# dcfsim.net
KiCad netlist of a schematic drawn in EAGLE
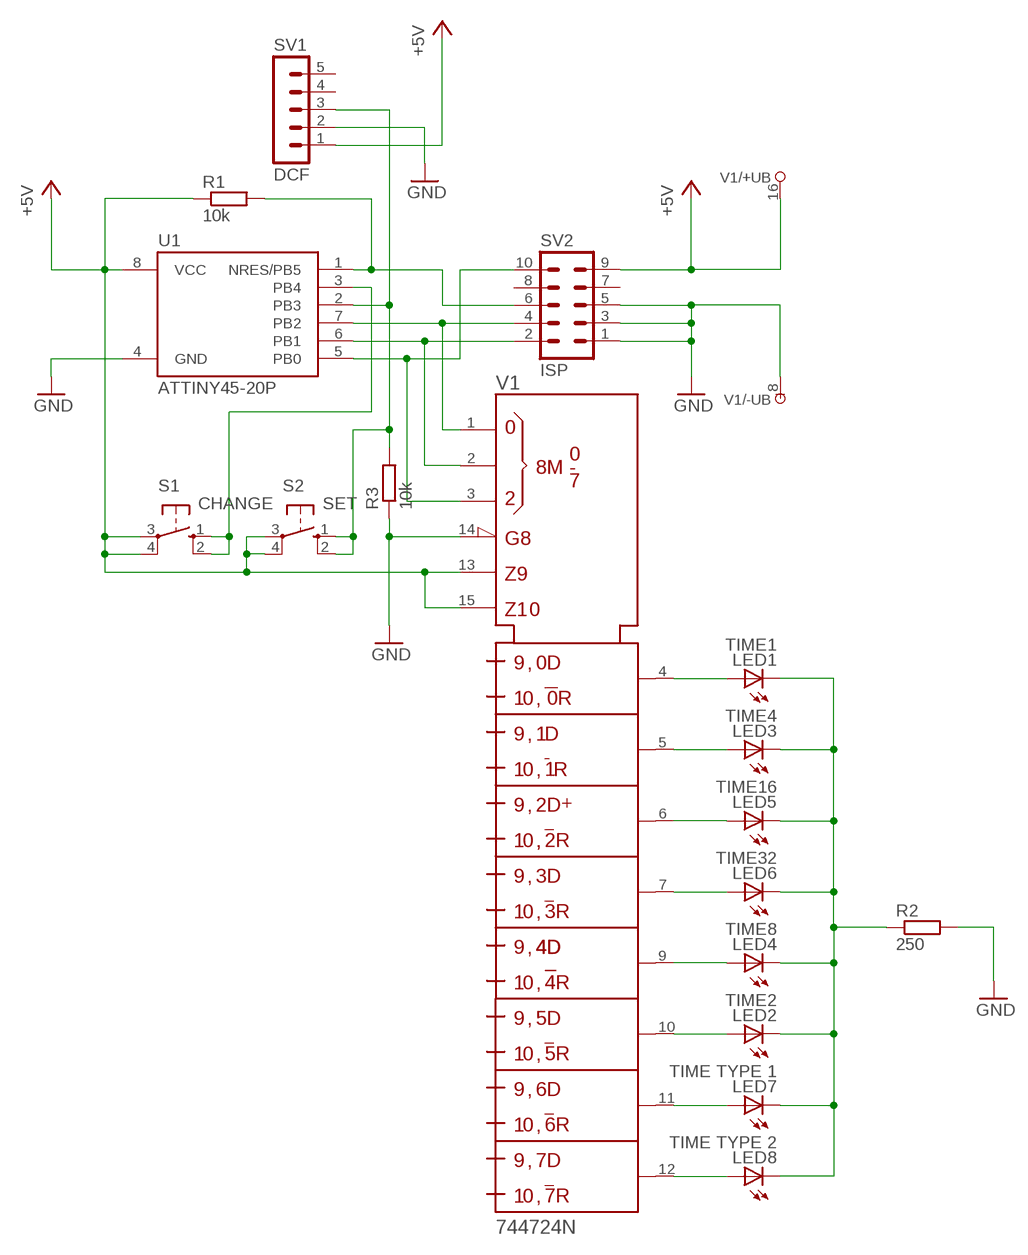
[diagram p0: schematic, sheet 1]

(export (version "E")
  (design (tool "Eeschema 10.0.6"))
  (components
    (comp (ref "LED1")
      (value "TIME1")
      (footprint "eagle-import:LED5MM")
      (libsource (lib "eagle-import") (part "LED5MM"))
    )
    (comp (ref "LED2")
      (value "TIME2")
      (footprint "eagle-import:LED5MM")
      (libsource (lib "eagle-import") (part "LED5MM"))
    )
    (comp (ref "LED3")
      (value "TIME4")
      (footprint "eagle-import:LED5MM")
      (libsource (lib "eagle-import") (part "LED5MM"))
    )
    (comp (ref "LED4")
      (value "TIME8")
      (footprint "eagle-import:LED5MM")
      (libsource (lib "eagle-import") (part "LED5MM"))
    )
    (comp (ref "LED5")
      (value "TIME16")
      (footprint "eagle-import:LED5MM")
      (libsource (lib "eagle-import") (part "LED5MM"))
    )
    (comp (ref "LED6")
      (value "TIME32")
      (footprint "eagle-import:LED5MM")
      (libsource (lib "eagle-import") (part "LED5MM"))
    )
    (comp (ref "LED7")
      (value "TIME TYPE 1")
      (footprint "eagle-import:LED5MM")
      (libsource (lib "eagle-import") (part "LED5MM"))
    )
    (comp (ref "LED8")
      (value "TIME TYPE 2")
      (footprint "eagle-import:LED5MM")
      (libsource (lib "eagle-import") (part "LED5MM"))
    )
    (comp (ref "R1")
      (value "10k")
      (footprint "eagle-import:0204_5")
      (libsource (lib "eagle-import") (part "R-EU_0204/5"))
    )
    (comp (ref "R2")
      (value "250")
      (footprint "eagle-import:0204_5")
      (libsource (lib "eagle-import") (part "R-EU_0204/5"))
    )
    (comp (ref "R3")
      (value "10k")
      (footprint "eagle-import:0204_5")
      (libsource (lib "eagle-import") (part "R-EU_0204/5"))
    )
    (comp (ref "S1")
      (value "CHANGE")
      (footprint "eagle-import:B3F-10XX")
      (fields (field (name "MPN") "B3F-1000"))
      (libsource (lib "eagle-import") (part "10-XX"))
    )
    (comp (ref "S2")
      (value "SET")
      (footprint "eagle-import:B3F-10XX")
      (fields (field (name "MPN") "B3F-1000"))
      (libsource (lib "eagle-import") (part "10-XX"))
    )
    (comp (ref "SV1")
      (value "DCF")
      (footprint "eagle-import:MA05-1")
      (libsource (lib "eagle-import") (part "MA05-1"))
    )
    (comp (ref "SV2")
      (value "ISP")
      (footprint "eagle-import:ML10")
      (libsource (lib "eagle-import") (part "ML10"))
    )
    (comp (ref "U1")
      (value "ATTINY45-20P")
      (footprint "eagle-import:PDIP08_300MIL")
      (libsource (lib "eagle-import") (part "ATTINY45P-20"))
    )
    (comp (ref "V1")
      (value "744724N")
      (footprint "eagle-import:DIL16")
      (libsource (lib "eagle-import") (part "744724N"))
    )
  )
  (nets
    (net (code "1") (name "+5V") (class "Default")
      (node (ref "R1") (pin "1") (pinfunction "1_1") (pintype "passive"))
      (node (ref "S1") (pin "3") (pinfunction "P_3") (pintype "passive"))
      (node (ref "S1") (pin "4") (pinfunction "P1_4") (pintype "passive"))
      (node (ref "S2") (pin "3") (pinfunction "P_3") (pintype "passive"))
      (node (ref "S2") (pin "4") (pinfunction "P1_4") (pintype "passive"))
      (node (ref "SV1") (pin "1") (pinfunction "1_1") (pintype "passive"))
      (node (ref "SV2") (pin "9") (pinfunction "9_9") (pintype "passive"))
      (node (ref "U1") (pin "8") (pinfunction "VCC_8") (pintype "power_in"))
      (node (ref "V1") (pin "13") (pinfunction "D_13") (pintype "input"))
      (node (ref "V1") (pin "15") (pinfunction "CLR_15") (pintype "input"))
      (node (ref "V1") (pin "16") (pinfunction "+UB_16") (pintype "power_in"))
    )
    (net (code "2") (name "GND") (class "Default")
      (node (ref "R2") (pin "2") (pinfunction "2_2") (pintype "passive"))
      (node (ref "R3") (pin "1") (pinfunction "1_1") (pintype "passive"))
      (node (ref "SV1") (pin "2") (pinfunction "2_2") (pintype "passive"))
      (node (ref "SV2") (pin "1") (pinfunction "1_1") (pintype "passive"))
      (node (ref "SV2") (pin "3") (pinfunction "3_3") (pintype "passive"))
      (node (ref "SV2") (pin "5") (pinfunction "5_5") (pintype "passive"))
      (node (ref "U1") (pin "4") (pinfunction "GND_4") (pintype "power_in"))
      (node (ref "V1") (pin "14") (pinfunction "~{G}_14") (pintype "input"))
      (node (ref "V1") (pin "8") (pinfunction "-UB_8") (pintype "power_in"))
    )
    (net (code "3") (name "Net-(LED1-C)") (class "Default")
      (node (ref "LED1") (pin "K") (pinfunction "C_K") (pintype "passive"))
      (node (ref "LED2") (pin "K") (pinfunction "C_K") (pintype "passive"))
      (node (ref "LED3") (pin "K") (pinfunction "C_K") (pintype "passive"))
      (node (ref "LED4") (pin "K") (pinfunction "C_K") (pintype "passive"))
      (node (ref "LED5") (pin "K") (pinfunction "C_K") (pintype "passive"))
      (node (ref "LED6") (pin "K") (pinfunction "C_K") (pintype "passive"))
      (node (ref "LED7") (pin "K") (pinfunction "C_K") (pintype "passive"))
      (node (ref "LED8") (pin "K") (pinfunction "C_K") (pintype "passive"))
      (node (ref "R2") (pin "1") (pinfunction "1_1") (pintype "passive"))
    )
    (net (code "4") (name "Net-(S1-S)") (class "Default")
      (node (ref "S1") (pin "1") (pinfunction "S_1") (pintype "passive"))
      (node (ref "S1") (pin "2") (pinfunction "S1_2") (pintype "passive"))
      (node (ref "U1") (pin "3") (pinfunction "PB4_3") (pintype "bidirectional"))
    )
    (net (code "5") (name "Net-(S2-S)") (class "Default")
      (node (ref "R3") (pin "2") (pinfunction "2_2") (pintype "passive"))
      (node (ref "S2") (pin "1") (pinfunction "S_1") (pintype "passive"))
      (node (ref "S2") (pin "2") (pinfunction "S1_2") (pintype "passive"))
      (node (ref "SV1") (pin "3") (pinfunction "3_3") (pintype "passive"))
      (node (ref "U1") (pin "2") (pinfunction "PB3_2") (pintype "bidirectional"))
    )
    (net (code "6") (name "Net-(U1-NRES{slash}PB5)") (class "Default")
      (node (ref "R1") (pin "2") (pinfunction "2_2") (pintype "passive"))
      (node (ref "SV2") (pin "6") (pinfunction "6_6") (pintype "passive"))
      (node (ref "U1") (pin "1") (pinfunction "NRES/PB5_1") (pintype "bidirectional"))
    )
    (net (code "7") (name "Net-(U1-PB0)") (class "Default")
      (node (ref "SV2") (pin "10") (pinfunction "10_10") (pintype "passive"))
      (node (ref "U1") (pin "5") (pinfunction "PB0_5") (pintype "bidirectional"))
      (node (ref "V1") (pin "3") (pinfunction "S2_3") (pintype "input"))
    )
    (net (code "8") (name "Net-(U1-PB1)") (class "Default")
      (node (ref "SV2") (pin "2") (pinfunction "2_2") (pintype "passive"))
      (node (ref "U1") (pin "6") (pinfunction "PB1_6") (pintype "bidirectional"))
      (node (ref "V1") (pin "2") (pinfunction "S1_2") (pintype "input"))
    )
    (net (code "9") (name "Net-(U1-PB2)") (class "Default")
      (node (ref "SV2") (pin "4") (pinfunction "4_4") (pintype "passive"))
      (node (ref "U1") (pin "7") (pinfunction "PB2_7") (pintype "bidirectional"))
      (node (ref "V1") (pin "1") (pinfunction "S0_1") (pintype "input"))
    )
    (net (code "10") (name "Net-(V1C-Q0)") (class "Default")
      (node (ref "LED1") (pin "A") (pinfunction "A_A") (pintype "passive"))
      (node (ref "V1") (pin "4") (pinfunction "Q0_4") (pintype "output"))
    )
    (net (code "11") (name "Net-(V1C-Q1)") (class "Default")
      (node (ref "LED3") (pin "A") (pinfunction "A_A") (pintype "passive"))
      (node (ref "V1") (pin "5") (pinfunction "Q1_5") (pintype "output"))
    )
    (net (code "12") (name "Net-(V1C-Q2)") (class "Default")
      (node (ref "LED5") (pin "A") (pinfunction "A_A") (pintype "passive"))
      (node (ref "V1") (pin "6") (pinfunction "Q2_6") (pintype "output"))
    )
    (net (code "13") (name "Net-(V1C-Q3)") (class "Default")
      (node (ref "LED6") (pin "A") (pinfunction "A_A") (pintype "passive"))
      (node (ref "V1") (pin "7") (pinfunction "Q3_7") (pintype "output"))
    )
    (net (code "14") (name "Net-(V1C-Q4)") (class "Default")
      (node (ref "LED4") (pin "A") (pinfunction "A_A") (pintype "passive"))
      (node (ref "V1") (pin "9") (pinfunction "Q4_9") (pintype "output"))
    )
    (net (code "15") (name "Net-(V1C-Q5)") (class "Default")
      (node (ref "LED2") (pin "A") (pinfunction "A_A") (pintype "passive"))
      (node (ref "V1") (pin "10") (pinfunction "Q5_10") (pintype "output"))
    )
    (net (code "16") (name "Net-(V1C-Q6)") (class "Default")
      (node (ref "LED7") (pin "A") (pinfunction "A_A") (pintype "passive"))
      (node (ref "V1") (pin "11") (pinfunction "Q6_11") (pintype "output"))
    )
    (net (code "17") (name "Net-(V1C-Q7)") (class "Default")
      (node (ref "LED8") (pin "A") (pinfunction "A_A") (pintype "passive"))
      (node (ref "V1") (pin "12") (pinfunction "Q7_12") (pintype "output"))
    )
    (net (code "18") (name "unconnected-(SV1-Pad4)") (class "Default")
      (node (ref "SV1") (pin "4") (pinfunction "4_4") (pintype "passive"))
    )
    (net (code "19") (name "unconnected-(SV1-Pad5)") (class "Default")
      (node (ref "SV1") (pin "5") (pinfunction "5_5") (pintype "passive"))
    )
    (net (code "20") (name "unconnected-(SV2-Pad7)") (class "Default")
      (node (ref "SV2") (pin "7") (pinfunction "7_7") (pintype "passive"))
    )
    (net (code "21") (name "unconnected-(SV2-Pad8)") (class "Default")
      (node (ref "SV2") (pin "8") (pinfunction "8_8") (pintype "passive"))
    )
  )
)
